# 2450_patch.net
KiCad netlist of a schematic drawn in Altium Designer
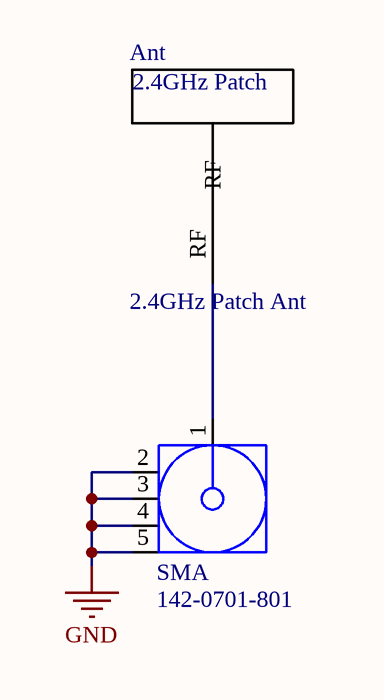
[diagram p0: 2450 patch.SchDoc]

(export (version "E")
  (design (tool "Eeschema 10.0.6"))
  (components
    (comp (ref "Ant")
      (value "2.4GHz Patch Ant")
      (footprint "jlcpcb 2.4GHz")
      (libsource (lib "PatchAntennas") (part "2.4GHz Patch Ant"))
    )
    (comp (ref "SMA")
      (value "142-0701-801")
      (footprint "CINC-142-0701-801_V")
      (description "SMA End Launch Jack Receptacle, 50 Ohm, 0 to 18 GHz, -65 to 165 degC, 5-Pin SMD, RoHS, Bulk")
      (fields (field (name "MANUFACTURER") "EmersonConnectivitySolutions"))
      (libsource (lib "Altium Content Vault") (part "CN-S-4F-RF5"))
    )
  )
  (nets
    (net (code "1") (name "GND") (class "Default")
      (node (ref "SMA") (pin "2") (pinfunction "2_2") (pintype "passive"))
      (node (ref "SMA") (pin "3") (pinfunction "3_3") (pintype "passive"))
      (node (ref "SMA") (pin "4") (pinfunction "4_4") (pintype "passive"))
      (node (ref "SMA") (pin "5") (pinfunction "5_5") (pintype "passive"))
    )
    (net (code "2") (name "Net-(Ant-PadRF)") (class "Default")
      (node (ref "Ant") (pin "RF") (pinfunction "RF_RF") (pintype "passive"))
      (node (ref "SMA") (pin "1") (pinfunction "1_1") (pintype "passive"))
    )
  )
)
